# logic.net
KiCad netlist of a schematic drawn in Altium Designer
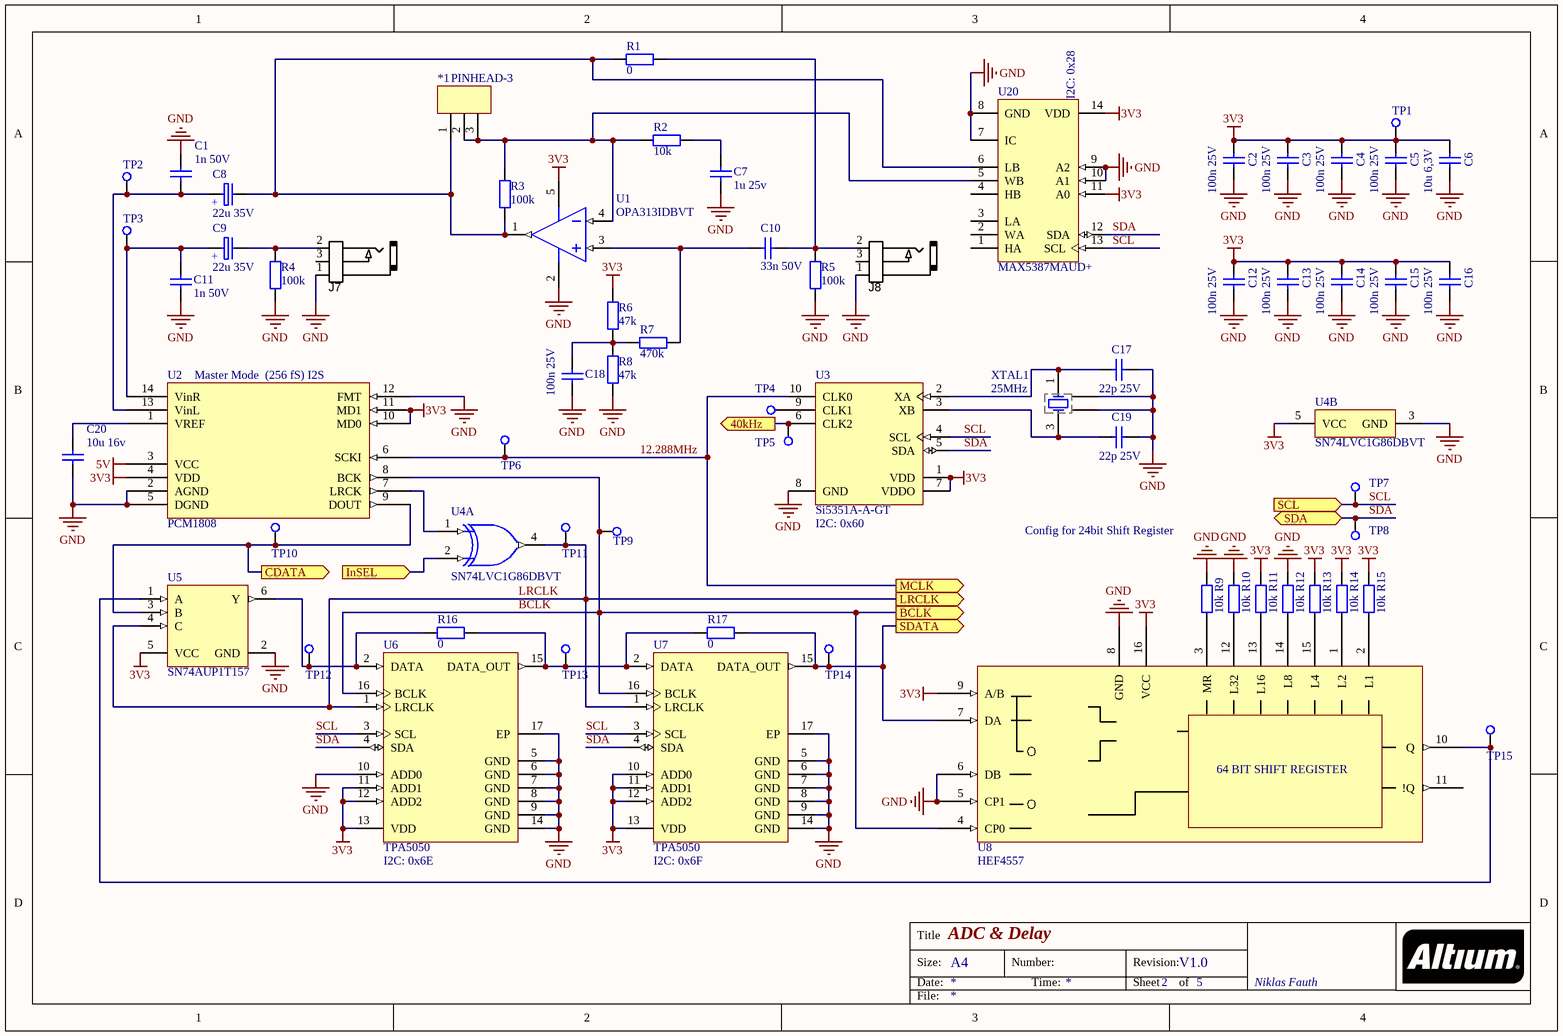
[diagram p0: logic.SchDoc]

(export (version "E")
  (design (tool "Eeschema 10.0.6"))
  (components
    (comp (ref "*1")
      (value "PINHEAD-3")
      (footprint "PINHEAD-3")
      (libsource (lib "advanced") (part "PINHEAD-3"))
    )
    (comp (ref "C1")
      (value "1n 50V")
      (footprint "C-0603-H")
      (description "Capacitor 1nF 50V")
      (libsource (lib "Passives") (part "C-0603-1n-50V"))
    )
    (comp (ref "C2")
      (value "100n 25V")
      (footprint "C-0603-H")
      (description "Capacitor 100n 25V")
      (libsource (lib "Passives") (part "C-0603-100n-25V"))
    )
    (comp (ref "C3")
      (value "100n 25V")
      (footprint "C-0603-H")
      (description "Capacitor 100n 25V")
      (libsource (lib "Passives") (part "C-0603-100n-25V"))
    )
    (comp (ref "C4")
      (value "100n 25V")
      (footprint "C-0603-H")
      (description "Capacitor 100n 25V")
      (libsource (lib "Passives") (part "C-0603-100n-25V"))
    )
    (comp (ref "C5")
      (value "100n 25V")
      (footprint "C-0603-H")
      (description "Capacitor 100n 25V")
      (libsource (lib "Passives") (part "C-0603-100n-25V"))
    )
    (comp (ref "C6")
      (value "10u 6,3V")
      (footprint "C-0603-H")
      (description "Capacitor 10uF 6,3V")
      (libsource (lib "Passives") (part "C-0603-10u-6,3V"))
    )
    (comp (ref "C7")
      (value "1u 25v")
      (footprint "C-0603-H")
      (description "Capacitor 1uF 25V")
      (libsource (lib "Passives") (part "C-0603-1u-25V"))
    )
    (comp (ref "C8")
      (value "22u 35V")
      (footprint "SMD-6.3-3.9")
      (description "electrolytic capacitor 22u 35V")
      (libsource (lib "Passives") (part "CE-SMD-22u-35V"))
    )
    (comp (ref "C9")
      (value "22u 35V")
      (footprint "SMD-6.3-3.9")
      (description "electrolytic capacitor 22u 35V")
      (libsource (lib "Passives") (part "CE-SMD-22u-35V"))
    )
    (comp (ref "C10")
      (value "33n 50V")
      (footprint "C-0603-M")
      (description "Capacitor 33nF 50V")
      (libsource (lib "Passives") (part "C-0603-33n-50V"))
    )
    (comp (ref "C11")
      (value "1n 50V")
      (footprint "C-0603-H")
      (description "Capacitor 1nF 50V")
      (libsource (lib "Passives") (part "C-0603-1n-50V"))
    )
    (comp (ref "C12")
      (value "100n 25V")
      (footprint "C-0603-H")
      (description "Capacitor 100n 25V")
      (libsource (lib "Passives") (part "C-0603-100n-25V"))
    )
    (comp (ref "C13")
      (value "100n 25V")
      (footprint "C-0603-H")
      (description "Capacitor 100n 25V")
      (libsource (lib "Passives") (part "C-0603-100n-25V"))
    )
    (comp (ref "C14")
      (value "100n 25V")
      (footprint "C-0603-H")
      (description "Capacitor 100n 25V")
      (libsource (lib "Passives") (part "C-0603-100n-25V"))
    )
    (comp (ref "C15")
      (value "100n 25V")
      (footprint "C-0603-H")
      (description "Capacitor 100n 25V")
      (libsource (lib "Passives") (part "C-0603-100n-25V"))
    )
    (comp (ref "C16")
      (value "100n 25V")
      (footprint "C-0603-H")
      (description "Capacitor 100n 25V")
      (libsource (lib "Passives") (part "C-0603-100n-25V"))
    )
    (comp (ref "C17")
      (value "22p 25V")
      (footprint "C-0402-M")
      (description "Capacitor 22pF 25V")
      (libsource (lib "Passives") (part "C-0402-22p-25V"))
    )
    (comp (ref "C18")
      (value "100n 25V")
      (footprint "C-0603-H")
      (description "Capacitor 100n 25V")
      (libsource (lib "Passives") (part "C-0603-100n-25V"))
    )
    (comp (ref "C19")
      (value "22p 25V")
      (footprint "C-0402-M")
      (description "Capacitor 22pF 25V")
      (libsource (lib "Passives") (part "C-0402-22p-25V"))
    )
    (comp (ref "C20")
      (value "10u 16v")
      (footprint "C-0603-H")
      (description "Capacitor 10uF 16v")
      (libsource (lib "Passives") (part "C-0603-10u-16v"))
    )
    (comp (ref "J7")
      (value "Mono phone jack")
      (footprint "CONN_AudioJackMono")
      (description "3.5mm Audio jack - Mono")
      (libsource (lib "PBL - Connectors") (part "CONN_AUDIOJACKMONO_3.5mm_RA_THD"))
    )
    (comp (ref "J8")
      (value "Mono phone jack")
      (footprint "CONN_AudioJackMono")
      (description "3.5mm Audio jack - Mono")
      (libsource (lib "PBL - Connectors") (part "CONN_AUDIOJACKMONO_3.5mm_RA_THD"))
    )
    (comp (ref "R1")
      (value "0")
      (footprint "R-0603-M")
      (description "Resistor 0")
      (libsource (lib "Passives") (part "R-0603-0"))
    )
    (comp (ref "R2")
      (value "10k")
      (footprint "R-0603-H")
      (description "Resistor 10k")
      (libsource (lib "Passives") (part "R-0603-10k"))
    )
    (comp (ref "R3")
      (value "100k")
      (footprint "R-0603-M")
      (description "Resistor 100k")
      (libsource (lib "Passives") (part "R-0603-100k"))
    )
    (comp (ref "R4")
      (value "100k")
      (footprint "R-0603-M")
      (description "Resistor 100k")
      (libsource (lib "Passives") (part "R-0603-100k"))
    )
    (comp (ref "R5")
      (value "100k")
      (footprint "R-0603-M")
      (description "Resistor 100k")
      (libsource (lib "Passives") (part "R-0603-100k"))
    )
    (comp (ref "R6")
      (value "47k")
      (footprint "R-0603-H")
      (description "Resistor 4k7")
      (libsource (lib "Passives") (part "R-0603-47k"))
    )
    (comp (ref "R7")
      (value "470k")
      (footprint "R-0603-H")
      (description "Resistor 470k")
      (libsource (lib "Passives") (part "R-0603-470k"))
    )
    (comp (ref "R8")
      (value "47k")
      (footprint "R-0603-H")
      (description "Resistor 4k7")
      (libsource (lib "Passives") (part "R-0603-47k"))
    )
    (comp (ref "R9")
      (value "10k")
      (footprint "R-0603-H")
      (description "Resistor 10k")
      (libsource (lib "") (part "R-0603-10k_1"))
    )
    (comp (ref "R10")
      (value "10k")
      (footprint "R-0603-H")
      (description "Resistor 10k")
      (libsource (lib "") (part "R-0603-10k_1"))
    )
    (comp (ref "R11")
      (value "10k")
      (footprint "R-0603-H")
      (description "Resistor 10k")
      (libsource (lib "") (part "R-0603-10k_1"))
    )
    (comp (ref "R12")
      (value "10k")
      (footprint "R-0603-H")
      (description "Resistor 10k")
      (libsource (lib "") (part "R-0603-10k_1"))
    )
    (comp (ref "R13")
      (value "10k")
      (footprint "R-0603-H")
      (description "Resistor 10k")
      (libsource (lib "") (part "R-0603-10k_1"))
    )
    (comp (ref "R14")
      (value "10k")
      (footprint "R-0603-H")
      (description "Resistor 10k")
      (libsource (lib "") (part "R-0603-10k_1"))
    )
    (comp (ref "R15")
      (value "10k")
      (footprint "R-0603-H")
      (description "Resistor 10k")
      (libsource (lib "") (part "R-0603-10k_1"))
    )
    (comp (ref "R16")
      (value "0")
      (footprint "R-0603-M")
      (description "Resistor 0")
      (libsource (lib "Passives") (part "R-0603-0"))
    )
    (comp (ref "R17")
      (value "0")
      (footprint "R-0603-M")
      (description "Resistor 0")
      (libsource (lib "Passives") (part "R-0603-0"))
    )
    (comp (ref "TP1") (value "TP-SMD") (footprint "TP") (libsource (lib "advanced") (part "TP-SMD")))
    (comp (ref "TP2") (value "TP-SMD") (footprint "TP") (libsource (lib "advanced") (part "TP-SMD")))
    (comp (ref "TP3") (value "TP-SMD") (footprint "TP") (libsource (lib "advanced") (part "TP-SMD")))
    (comp (ref "TP4") (value "TP-SMD") (footprint "TP") (libsource (lib "advanced") (part "TP-SMD")))
    (comp (ref "TP5") (value "TP-SMD") (footprint "TP") (libsource (lib "advanced") (part "TP-SMD")))
    (comp (ref "TP6") (value "TP-SMD") (footprint "TP") (libsource (lib "advanced") (part "TP-SMD")))
    (comp (ref "TP7") (value "TP-SMD") (footprint "TP") (libsource (lib "advanced") (part "TP-SMD")))
    (comp (ref "TP8") (value "TP-SMD") (footprint "TP") (libsource (lib "advanced") (part "TP-SMD")))
    (comp (ref "TP9") (value "TP-SMD") (footprint "TP") (libsource (lib "advanced") (part "TP-SMD")))
    (comp (ref "TP10") (value "TP-SMD") (footprint "TP") (libsource (lib "advanced") (part "TP-SMD")))
    (comp (ref "TP11") (value "TP-SMD") (footprint "TP") (libsource (lib "advanced") (part "TP-SMD")))
    (comp (ref "TP12") (value "TP-SMD") (footprint "TP") (libsource (lib "advanced") (part "TP-SMD")))
    (comp (ref "TP13") (value "TP-SMD") (footprint "TP") (libsource (lib "advanced") (part "TP-SMD")))
    (comp (ref "TP14") (value "TP-SMD") (footprint "TP") (libsource (lib "advanced") (part "TP-SMD")))
    (comp (ref "TP15") (value "TP-SMD") (footprint "TP") (libsource (lib "advanced") (part "TP-SMD")))
    (comp (ref "U1")
      (value "OPA313IDBVT")
      (footprint "DBV0005A_M")
      (fields (field (name "MANUFACTURER") "Texas Instruments"))
      (libsource (lib "Altium Content Vault") (part "TI-OPA313-DBV5"))
    )
    (comp (ref "U2")
      (value "PCM1808")
      (footprint "TSOP65P640X120-14N")
      (libsource (lib "400PT160_2") (part "PCM1808"))
    )
    (comp (ref "U3")
      (value "Si5351A-A-GT")
      (footprint "SLAB-MSOP-10_M")
      (fields (field (name "MANUFACTURER") "Silicon Labs"))
      (libsource (lib "Altium Content Vault") (part "SLAB-Si5351-MSOP-10-10"))
    )
    (comp (ref "U4")
      (value "SN74LVC1G86DBVT")
      (footprint "DBV0005A_N")
      (description "Single 2-Input Exclusive-OR Gate, DBV0005A, SMALL T&R")
      (fields
        (field (name "GENERIC PART NUMBER") "SN74LVC1G86")
        (field (name "MANUFACTURER") "Texas Instruments")
      )
      (libsource (lib "Altium Content Vault") (part "TI-XOR-1-2IN-5"))
    )
    (comp (ref "U5")
      (value "SN74AUP1T157")
      (footprint "DCK0006A_M")
      (description "Low Power, 1.8/2.5/3.3-V In, 3.3-V CMOS Out, Buffer Multiplexer (Noninverted), DCK0006A, LARGE T&R")
      (fields (field (name "MANUFACTURER") "Texas Instruments"))
      (libsource (lib "Altium Content Vault") (part "TI-SN74AUP1T157-DCK0006A-6"))
    )
    (comp (ref "U6")
      (value "TPA5050")
      (footprint "QFN16-4x4-0.65 big holes")
      (libsource (lib "advanced") (part "TPA5050"))
    )
    (comp (ref "U7")
      (value "TPA5050")
      (footprint "QFN16-4x4-0.65 big holes")
      (libsource (lib "advanced") (part "TPA5050"))
    )
    (comp (ref "U8")
      (value "HEF4557")
      (footprint "SOIC127P600X265-16N")
      (libsource (lib "400PT160_2") (part "HEF4557"))
    )
    (comp (ref "U20")
      (value "MAX5387MAUD+")
      (footprint "MAXM-U14+1_N")
      (libsource (lib "Altium Content Vault") (part "CMP-0022-00051-1"))
    )
    (comp (ref "XTAL1") (value "25MHz") (footprint "ABM11") (libsource (lib "advanced") (part "ABM11-25MHz")))
  )
  (nets
    (net (code "1") (name "/12.288MHz") (class "Default")
      (node (ref "TP6") (pin "1") (pintype "passive"))
      (node (ref "U2") (pin "6") (pinfunction "SCKI_6") (pintype "input"))
      (node (ref "U3") (pin "10") (pinfunction "CLK0_10") (pintype "tri_state"))
    )
    (net (code "2") (name "/40kHz") (class "Default")
      (node (ref "TP5") (pin "1") (pintype "passive"))
      (node (ref "U3") (pin "6") (pinfunction "CLK2_6") (pintype "tri_state"))
    )
    (net (code "3") (name "/BCLK") (class "Default")
      (node (ref "TP9") (pin "1") (pintype "passive"))
      (node (ref "U2") (pin "8") (pinfunction "BCK_8") (pintype "output"))
      (node (ref "U6") (pin "16") (pinfunction "BCLK_16") (pintype "input"))
      (node (ref "U7") (pin "16") (pinfunction "BCLK_16") (pintype "input"))
      (node (ref "U8") (pin "4") (pinfunction "CP0_4") (pintype "input"))
    )
    (net (code "4") (name "/CDATA") (class "Default")
      (node (ref "TP10") (pin "1") (pintype "passive"))
      (node (ref "U2") (pin "9") (pinfunction "DOUT_9") (pintype "output"))
      (node (ref "U5") (pin "3") (pinfunction "B_3") (pintype "input"))
    )
    (net (code "5") (name "/InSEL") (class "Default")
      (node (ref "U4") (pin "2") (pinfunction "B_2") (pintype "input"))
    )
    (net (code "6") (name "/LRCLK") (class "Default")
      (node (ref "TP11") (pin "1") (pintype "passive"))
      (node (ref "U4") (pin "4") (pinfunction "Y_4") (pintype "output"))
      (node (ref "U5") (pin "4") (pinfunction "C_4") (pintype "input"))
      (node (ref "U6") (pin "1") (pinfunction "LRCLK_1") (pintype "input"))
      (node (ref "U7") (pin "1") (pinfunction "LRCLK_1") (pintype "input"))
    )
    (net (code "7") (name "/SCL") (class "Default")
      (node (ref "TP7") (pin "1") (pintype "passive"))
      (node (ref "U20") (pin "13") (pinfunction "SCL_13") (pintype "input"))
      (node (ref "U3") (pin "4") (pinfunction "SCL_4") (pintype "input"))
      (node (ref "U6") (pin "3") (pinfunction "SCL_3") (pintype "input"))
      (node (ref "U7") (pin "3") (pinfunction "SCL_3") (pintype "input"))
    )
    (net (code "8") (name "/SDA") (class "Default")
      (node (ref "TP8") (pin "1") (pintype "passive"))
      (node (ref "U20") (pin "12") (pinfunction "SDA_12") (pintype "bidirectional"))
      (node (ref "U3") (pin "5") (pinfunction "SDA_5") (pintype "bidirectional"))
      (node (ref "U6") (pin "4") (pinfunction "SDA_4") (pintype "bidirectional"))
      (node (ref "U7") (pin "4") (pinfunction "SDA_4") (pintype "bidirectional"))
    )
    (net (code "9") (name "/SDATA") (class "Default")
      (node (ref "R17") (pin "2") (pinfunction "2_2") (pintype "passive"))
      (node (ref "TP14") (pin "1") (pintype "passive"))
      (node (ref "U7") (pin "15") (pinfunction "DATA_OUT_15") (pintype "output"))
      (node (ref "U8") (pin "7") (pinfunction "DA_7") (pintype "input"))
    )
    (net (code "10") (name "3V3") (class "Default")
      (node (ref "C12") (pin "2") (pinfunction "2_2") (pintype "passive"))
      (node (ref "C13") (pin "2") (pinfunction "2_2") (pintype "passive"))
      (node (ref "C14") (pin "2") (pinfunction "2_2") (pintype "passive"))
      (node (ref "C15") (pin "2") (pinfunction "2_2") (pintype "passive"))
      (node (ref "C16") (pin "2") (pinfunction "2_2") (pintype "passive"))
      (node (ref "C2") (pin "2") (pinfunction "2_2") (pintype "passive"))
      (node (ref "C3") (pin "2") (pinfunction "2_2") (pintype "passive"))
      (node (ref "C4") (pin "2") (pinfunction "2_2") (pintype "passive"))
      (node (ref "C5") (pin "2") (pinfunction "2_2") (pintype "passive"))
      (node (ref "C6") (pin "2") (pinfunction "2_2") (pintype "passive"))
      (node (ref "R11") (pin "2") (pinfunction "2_2") (pintype "passive"))
      (node (ref "R13") (pin "2") (pinfunction "2_2") (pintype "passive"))
      (node (ref "R14") (pin "2") (pinfunction "2_2") (pintype "passive"))
      (node (ref "R15") (pin "2") (pinfunction "2_2") (pintype "passive"))
      (node (ref "R6") (pin "2") (pinfunction "2_2") (pintype "passive"))
      (node (ref "TP1") (pin "1") (pintype "passive"))
      (node (ref "U1") (pin "5") (pinfunction "V+_5") (pintype "power_in"))
      (node (ref "U2") (pin "10") (pinfunction "MD0_10") (pintype "input"))
      (node (ref "U2") (pin "11") (pinfunction "MD1_11") (pintype "input"))
      (node (ref "U2") (pin "4") (pinfunction "VDD_4") (pintype "power_in"))
      (node (ref "U20") (pin "11") (pinfunction "A0_11") (pintype "input"))
      (node (ref "U20") (pin "14") (pinfunction "VDD_14") (pintype "power_in"))
      (node (ref "U3") (pin "1") (pinfunction "VDD_1") (pintype "power_in"))
      (node (ref "U3") (pin "7") (pinfunction "VDDO_7") (pintype "power_in"))
      (node (ref "U4") (pin "5") (pinfunction "VCC_5") (pintype "power_in"))
      (node (ref "U5") (pin "5") (pinfunction "VCC_5") (pintype "power_in"))
      (node (ref "U6") (pin "11") (pinfunction "ADD1_11") (pintype "input"))
      (node (ref "U6") (pin "12") (pinfunction "ADD2_12") (pintype "input"))
      (node (ref "U6") (pin "13") (pinfunction "VDD_13") (pintype "power_in"))
      (node (ref "U7") (pin "10") (pinfunction "ADD0_10") (pintype "input"))
      (node (ref "U7") (pin "11") (pinfunction "ADD1_11") (pintype "input"))
      (node (ref "U7") (pin "12") (pinfunction "ADD2_12") (pintype "input"))
      (node (ref "U7") (pin "13") (pinfunction "VDD_13") (pintype "power_in"))
      (node (ref "U8") (pin "16") (pinfunction "VCC_16") (pintype "passive"))
      (node (ref "U8") (pin "9") (pinfunction "A/B_9") (pintype "input"))
    )
    (net (code "11") (name "5V") (class "Default")
      (node (ref "U2") (pin "3") (pinfunction "VCC_3") (pintype "power_in"))
    )
    (net (code "12") (name "GND") (class "Default")
      (node (ref "C1") (pin "2") (pinfunction "2_2") (pintype "passive"))
      (node (ref "C11") (pin "2") (pinfunction "2_2") (pintype "passive"))
      (node (ref "C12") (pin "1") (pinfunction "1_1") (pintype "passive"))
      (node (ref "C13") (pin "1") (pinfunction "1_1") (pintype "passive"))
      (node (ref "C14") (pin "1") (pinfunction "1_1") (pintype "passive"))
      (node (ref "C15") (pin "1") (pinfunction "1_1") (pintype "passive"))
      (node (ref "C16") (pin "1") (pinfunction "1_1") (pintype "passive"))
      (node (ref "C17") (pin "2") (pinfunction "2_2") (pintype "passive"))
      (node (ref "C18") (pin "1") (pinfunction "1_1") (pintype "passive"))
      (node (ref "C19") (pin "2") (pinfunction "2_2") (pintype "passive"))
      (node (ref "C2") (pin "1") (pinfunction "1_1") (pintype "passive"))
      (node (ref "C20") (pin "1") (pinfunction "1_1") (pintype "passive"))
      (node (ref "C3") (pin "1") (pinfunction "1_1") (pintype "passive"))
      (node (ref "C4") (pin "1") (pinfunction "1_1") (pintype "passive"))
      (node (ref "C5") (pin "1") (pinfunction "1_1") (pintype "passive"))
      (node (ref "C6") (pin "1") (pinfunction "1_1") (pintype "passive"))
      (node (ref "C7") (pin "1") (pinfunction "1_1") (pintype "passive"))
      (node (ref "J7") (pin "1") (pinfunction "Base_1") (pintype "passive"))
      (node (ref "J8") (pin "1") (pinfunction "Base_1") (pintype "passive"))
      (node (ref "R10") (pin "2") (pinfunction "2_2") (pintype "passive"))
      (node (ref "R12") (pin "2") (pinfunction "2_2") (pintype "passive"))
      (node (ref "R4") (pin "1") (pinfunction "1_1") (pintype "passive"))
      (node (ref "R5") (pin "1") (pinfunction "1_1") (pintype "passive"))
      (node (ref "R8") (pin "1") (pinfunction "1_1") (pintype "passive"))
      (node (ref "R9") (pin "2") (pinfunction "2_2") (pintype "passive"))
      (node (ref "U1") (pin "2") (pinfunction "V-_2") (pintype "power_in"))
      (node (ref "U2") (pin "12") (pinfunction "FMT_12") (pintype "input"))
      (node (ref "U2") (pin "2") (pinfunction "AGND_2") (pintype "passive"))
      (node (ref "U2") (pin "5") (pinfunction "DGND_5") (pintype "power_in"))
      (node (ref "U20") (pin "10") (pinfunction "A1_10") (pintype "input"))
      (node (ref "U20") (pin "7") (pinfunction "IC_7") (pintype "passive"))
      (node (ref "U20") (pin "8") (pinfunction "GND_8") (pintype "power_in"))
      (node (ref "U20") (pin "9") (pinfunction "A2_9") (pintype "input"))
      (node (ref "U3") (pin "8") (pinfunction "GND_8") (pintype "power_in"))
      (node (ref "U4") (pin "3") (pinfunction "GND_3") (pintype "power_in"))
      (node (ref "U5") (pin "2") (pinfunction "GND_2") (pintype "power_in"))
      (node (ref "U6") (pin "10") (pinfunction "ADD0_10") (pintype "input"))
      (node (ref "U6") (pin "14") (pinfunction "GND_14") (pintype "power_in"))
      (node (ref "U6") (pin "17") (pinfunction "EP_17") (pintype "power_in"))
      (node (ref "U6") (pin "5") (pinfunction "GND_5") (pintype "power_in"))
      (node (ref "U6") (pin "6") (pinfunction "GND_6") (pintype "power_in"))
      (node (ref "U6") (pin "7") (pinfunction "GND_7") (pintype "power_in"))
      (node (ref "U6") (pin "8") (pinfunction "GND_8") (pintype "power_in"))
      (node (ref "U6") (pin "9") (pinfunction "GND_9") (pintype "power_in"))
      (node (ref "U7") (pin "14") (pinfunction "GND_14") (pintype "power_in"))
      (node (ref "U7") (pin "17") (pinfunction "EP_17") (pintype "power_in"))
      (node (ref "U7") (pin "5") (pinfunction "GND_5") (pintype "power_in"))
      (node (ref "U7") (pin "6") (pinfunction "GND_6") (pintype "power_in"))
      (node (ref "U7") (pin "7") (pinfunction "GND_7") (pintype "power_in"))
      (node (ref "U7") (pin "8") (pinfunction "GND_8") (pintype "power_in"))
      (node (ref "U7") (pin "9") (pinfunction "GND_9") (pintype "power_in"))
      (node (ref "U8") (pin "5") (pinfunction "CP1_5") (pintype "input"))
      (node (ref "U8") (pin "6") (pinfunction "DB_6") (pintype "input"))
      (node (ref "U8") (pin "8") (pinfunction "GND_8") (pintype "passive"))
      (node (ref "XTAL1") (pin "2") (pintype "power_in"))
      (node (ref "XTAL1") (pin "4") (pintype "power_in"))
    )
    (net (code "13") (name "Net-(C7-Pad2)") (class "Default")
      (node (ref "C7") (pin "2") (pinfunction "2_2") (pintype "passive"))
      (node (ref "R2") (pin "2") (pinfunction "2_2") (pintype "passive"))
    )
    (net (code "14") (name "Net-(C18-Pad2)") (class "Default")
      (node (ref "C18") (pin "2") (pinfunction "2_2") (pintype "passive"))
      (node (ref "R6") (pin "1") (pinfunction "1_1") (pintype "passive"))
      (node (ref "R7") (pin "2") (pinfunction "2_2") (pintype "passive"))
      (node (ref "R8") (pin "2") (pinfunction "2_2") (pintype "passive"))
    )
    (net (code "15") (name "Net-(J7-TIP)") (class "Default")
      (node (ref "C9") (pin "1") (pinfunction "1_1") (pintype "passive"))
      (node (ref "J7") (pin "2") (pinfunction "TIP_2") (pintype "passive"))
      (node (ref "R4") (pin "2") (pinfunction "2_2") (pintype "passive"))
    )
    (net (code "16") (name "Net-(J8-TIP)") (class "Default")
      (node (ref "C10") (pin "2") (pinfunction "2_2") (pintype "passive"))
      (node (ref "J8") (pin "2") (pinfunction "TIP_2") (pintype "passive"))
      (node (ref "R1") (pin "2") (pinfunction "2_2") (pintype "passive"))
      (node (ref "R5") (pin "2") (pinfunction "2_2") (pintype "passive"))
    )
    (net (code "17") (name "Net-(U1-IN+)") (class "Default")
      (node (ref "C10") (pin "1") (pinfunction "1_1") (pintype "passive"))
      (node (ref "R7") (pin "1") (pinfunction "1_1") (pintype "passive"))
      (node (ref "U1") (pin "3") (pinfunction "IN+_3") (pintype "input"))
    )
    (net (code "18") (name "Net-(U1-IN-)") (class "Default")
      (node (ref "*1") (pin "2") (pintype "passive"))
      (node (ref "*1") (pin "3") (pintype "passive"))
      (node (ref "R2") (pin "1") (pinfunction "1_1") (pintype "passive"))
      (node (ref "R3") (pin "2") (pinfunction "2_2") (pintype "passive"))
      (node (ref "U1") (pin "4") (pinfunction "IN-_4") (pintype "input"))
      (node (ref "U20") (pin "5") (pinfunction "WB_5") (pintype "passive"))
    )
    (net (code "19") (name "Net-(U1-OUT)") (class "Default")
      (node (ref "*1") (pin "1") (pintype "passive"))
      (node (ref "C8") (pin "1") (pinfunction "1_1") (pintype "passive"))
      (node (ref "R1") (pin "1") (pinfunction "1_1") (pintype "passive"))
      (node (ref "R3") (pin "1") (pinfunction "1_1") (pintype "passive"))
      (node (ref "U1") (pin "1") (pinfunction "OUT_1") (pintype "output"))
      (node (ref "U20") (pin "6") (pinfunction "LB_6") (pintype "passive"))
    )
    (net (code "20") (name "Net-(U2-LRCK)") (class "Default")
      (node (ref "U2") (pin "7") (pinfunction "LRCK_7") (pintype "output"))
      (node (ref "U4") (pin "1") (pinfunction "A_1") (pintype "input"))
    )
    (net (code "21") (name "Net-(U2-VREF)") (class "Default")
      (node (ref "C20") (pin "2") (pinfunction "2_2") (pintype "passive"))
      (node (ref "U2") (pin "1") (pinfunction "VREF_1") (pintype "passive"))
    )
    (net (code "22") (name "Net-(U2-VinL)") (class "Default")
      (node (ref "C1") (pin "1") (pinfunction "1_1") (pintype "passive"))
      (node (ref "C8") (pin "2") (pinfunction "2_2") (pintype "passive"))
      (node (ref "TP2") (pin "1") (pintype "passive"))
      (node (ref "U2") (pin "13") (pinfunction "VinL_13") (pintype "passive"))
    )
    (net (code "23") (name "Net-(U2-VinR)") (class "Default")
      (node (ref "C11") (pin "1") (pinfunction "1_1") (pintype "passive"))
      (node (ref "C9") (pin "2") (pinfunction "2_2") (pintype "passive"))
      (node (ref "TP3") (pin "1") (pintype "passive"))
      (node (ref "U2") (pin "14") (pinfunction "VinR_14") (pintype "passive"))
    )
    (net (code "24") (name "Net-(U3-CLK1)") (class "Default")
      (node (ref "TP4") (pin "1") (pintype "passive"))
      (node (ref "U3") (pin "9") (pinfunction "CLK1_9") (pintype "tri_state"))
    )
    (net (code "25") (name "Net-(U3-XA)") (class "Default")
      (node (ref "C17") (pin "1") (pinfunction "1_1") (pintype "passive"))
      (node (ref "U3") (pin "2") (pinfunction "XA_2") (pintype "input"))
      (node (ref "XTAL1") (pin "1") (pintype "power_in"))
    )
    (net (code "26") (name "Net-(U3-XB)") (class "Default")
      (node (ref "C19") (pin "1") (pinfunction "1_1") (pintype "passive"))
      (node (ref "U3") (pin "3") (pinfunction "XB_3") (pintype "passive"))
      (node (ref "XTAL1") (pin "3") (pintype "power_in"))
    )
    (net (code "27") (name "Net-(U5-A)") (class "Default")
      (node (ref "TP15") (pin "1") (pintype "passive"))
      (node (ref "U5") (pin "1") (pinfunction "A_1") (pintype "input"))
      (node (ref "U8") (pin "10") (pinfunction "Q_10") (pintype "output"))
    )
    (net (code "28") (name "Net-(U5-Y)") (class "Default")
      (node (ref "R16") (pin "1") (pinfunction "1_1") (pintype "passive"))
      (node (ref "TP12") (pin "1") (pintype "passive"))
      (node (ref "U5") (pin "6") (pinfunction "Y_6") (pintype "output"))
      (node (ref "U6") (pin "2") (pinfunction "DATA_2") (pintype "input"))
    )
    (net (code "29") (name "Net-(U6-DATA_OUT)") (class "Default")
      (node (ref "R16") (pin "2") (pinfunction "2_2") (pintype "passive"))
      (node (ref "R17") (pin "1") (pinfunction "1_1") (pintype "passive"))
      (node (ref "TP13") (pin "1") (pintype "passive"))
      (node (ref "U6") (pin "15") (pinfunction "DATA_OUT_15") (pintype "output"))
      (node (ref "U7") (pin "2") (pinfunction "DATA_2") (pintype "input"))
    )
    (net (code "30") (name "Net-(U8-L1)") (class "Default")
      (node (ref "R15") (pin "1") (pinfunction "1_1") (pintype "passive"))
      (node (ref "U8") (pin "2") (pinfunction "L1_2") (pintype "passive"))
    )
    (net (code "31") (name "Net-(U8-L2)") (class "Default")
      (node (ref "R14") (pin "1") (pinfunction "1_1") (pintype "passive"))
      (node (ref "U8") (pin "1") (pinfunction "L2_1") (pintype "passive"))
    )
    (net (code "32") (name "Net-(U8-L4)") (class "Default")
      (node (ref "R13") (pin "1") (pinfunction "1_1") (pintype "passive"))
      (node (ref "U8") (pin "15") (pinfunction "L4_15") (pintype "passive"))
    )
    (net (code "33") (name "Net-(U8-L8)") (class "Default")
      (node (ref "R12") (pin "1") (pinfunction "1_1") (pintype "passive"))
      (node (ref "U8") (pin "14") (pinfunction "L8_14") (pintype "passive"))
    )
    (net (code "34") (name "Net-(U8-L16)") (class "Default")
      (node (ref "R11") (pin "1") (pinfunction "1_1") (pintype "passive"))
      (node (ref "U8") (pin "13") (pinfunction "L16_13") (pintype "passive"))
    )
    (net (code "35") (name "Net-(U8-L32)") (class "Default")
      (node (ref "R10") (pin "1") (pinfunction "1_1") (pintype "passive"))
      (node (ref "U8") (pin "12") (pinfunction "L32_12") (pintype "passive"))
    )
    (net (code "36") (name "Net-(U8-MR)") (class "Default")
      (node (ref "R9") (pin "1") (pinfunction "1_1") (pintype "passive"))
      (node (ref "U8") (pin "3") (pinfunction "MR_3") (pintype "passive"))
    )
    (net (code "37") (name "unconnected-(J7-Middle-Pad3)") (class "Default")
      (node (ref "J7") (pin "3") (pinfunction "Middle_3") (pintype "passive"))
    )
    (net (code "38") (name "unconnected-(J8-Middle-Pad3)") (class "Default")
      (node (ref "J8") (pin "3") (pinfunction "Middle_3") (pintype "passive"))
    )
    (net (code "39") (name "unconnected-(U8-!Q-Pad11)") (class "Default")
      (node (ref "U8") (pin "11") (pinfunction "!Q_11") (pintype "output"))
    )
    (net (code "40") (name "unconnected-(U20-HA-Pad1)") (class "Default")
      (node (ref "U20") (pin "1") (pinfunction "HA_1") (pintype "passive"))
    )
    (net (code "41") (name "unconnected-(U20-HB-Pad4)") (class "Default")
      (node (ref "U20") (pin "4") (pinfunction "HB_4") (pintype "passive"))
    )
    (net (code "42") (name "unconnected-(U20-LA-Pad3)") (class "Default")
      (node (ref "U20") (pin "3") (pinfunction "LA_3") (pintype "passive"))
    )
    (net (code "43") (name "unconnected-(U20-WA-Pad2)") (class "Default")
      (node (ref "U20") (pin "2") (pinfunction "WA_2") (pintype "passive"))
    )
  )
)
